# LPCB235_-_OPTONCDT_-_GROUP_B.net
KiCad netlist of a schematic drawn in Altium Designer
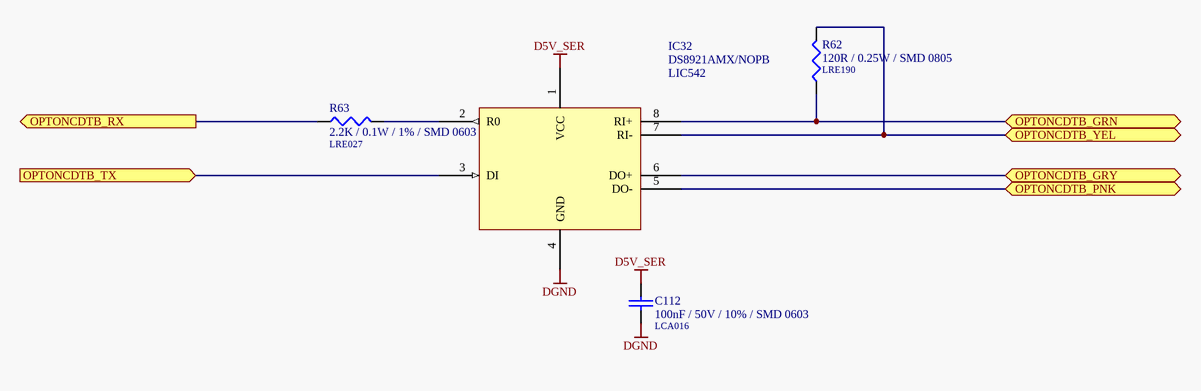
[diagram p0: LPCB235 - OPTONCDT - GROUP B.SchDoc]

(export (version "E")
  (design (tool "Eeschema 10.0.6"))
  (components
    (comp (ref "C112")
      (value "100nF / 50V / 10% / SMD 0603")
      (footprint "LFP011__CC1608-0603-IPC7351_B")
      (description "Capacitor, Ceramic Chip, 100nF (0.1uF), 50V, 5%, SMD 0603 [LCA016]")
      (fields (field (name "LDL_NUMBER") "LCA016"))
      (libsource (lib "LDL_Capacitors") (part "100nF / 50V / 10% / SMD 0603"))
    )
    (comp (ref "IC32")
      (value "DS8921AMX/NOPB")
      (footprint "LFP069__R-8G")
      (description "IC, RS422 Tx Rx, SMD SOIC 8")
      (fields (field (name "LDL_NUMBER") "LIC542"))
      (libsource (lib "LDL_Semiconductors") (part "DS8921AMX/NOPB"))
    )
    (comp (ref "R62")
      (value "120R / 0.25W / SMD 0805")
      (footprint "LFP029__CR2012-0805")
      (description "Resistor, Thick Film, 120R, 0.25W, 5%, SMD 0805 [LRE190]")
      (fields (field (name "LDL_NUMBER") "LRE190"))
      (libsource (lib "LDL_Resistors") (part "120R / 0.25W / SMD 0805"))
    )
    (comp (ref "R63")
      (value "2.2K / 0.1W / 1% / SMD 0603")
      (footprint "LFP020__CR1608-0603-IPC7351_B")
      (description "Resistor, Ceramic Chip, 2.2K, 0.1W, 1%, SMD 0603 [LRE027]")
      (fields (field (name "LDL_NUMBER") "LRE027"))
      (libsource (lib "LDL_Resistors") (part "2.2K / 0.1W / 1% / SMD 0603"))
    )
  )
  (nets
    (net (code "1") (name "/OPTONCDTB_GRN") (class "Default")
      (node (ref "IC32") (pin "8") (pinfunction "RI+_8") (pintype "passive"))
      (node (ref "R62") (pin "1") (pintype "passive"))
    )
    (net (code "2") (name "/OPTONCDTB_GRY") (class "Default")
      (node (ref "IC32") (pin "6") (pinfunction "DO+_6") (pintype "passive"))
    )
    (net (code "3") (name "/OPTONCDTB_PNK") (class "Default")
      (node (ref "IC32") (pin "5") (pinfunction "DO-_5") (pintype "passive"))
    )
    (net (code "4") (name "/OPTONCDTB_RX") (class "Default") (node (ref "R63") (pin "1") (pintype "passive")))
    (net (code "5") (name "/OPTONCDTB_TX") (class "Default")
      (node (ref "IC32") (pin "3") (pinfunction "DI_3") (pintype "input"))
    )
    (net (code "6") (name "/OPTONCDTB_YEL") (class "Default")
      (node (ref "IC32") (pin "7") (pinfunction "RI-_7") (pintype "passive"))
      (node (ref "R62") (pin "2") (pintype "passive"))
    )
    (net (code "7") (name "D5V_SER") (class "Default")
      (node (ref "C112") (pin "1") (pintype "passive"))
      (node (ref "IC32") (pin "1") (pinfunction "VCC_1") (pintype "power_in"))
    )
    (net (code "8") (name "DGND") (class "Default")
      (node (ref "C112") (pin "2") (pintype "passive"))
      (node (ref "IC32") (pin "4") (pinfunction "GND_4") (pintype "power_in"))
    )
    (net (code "9") (name "Net-(IC32-R0)") (class "Default")
      (node (ref "IC32") (pin "2") (pinfunction "R0_2") (pintype "output"))
      (node (ref "R63") (pin "2") (pintype "passive"))
    )
  )
)
